# smart-switch.net
KiCad netlist of a schematic drawn in Altium Designer
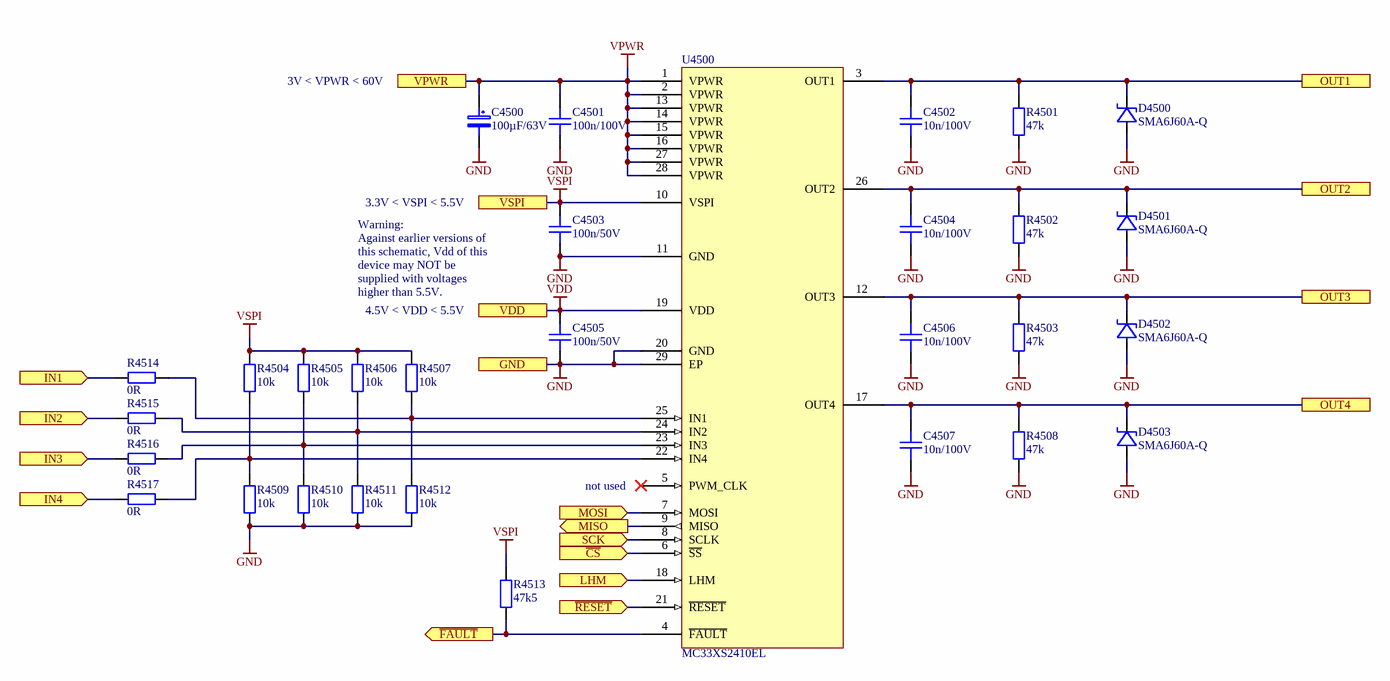
[diagram p0: smart-switch.SchDoc]

(export (version "E")
  (design (tool "Eeschema 10.0.6"))
  (components
    (comp (ref "C4500")
      (value "100µF/63V")
      (footprint "ELECTROLYTIC_CAP_PANASONIC_G")
      (description "SMD Electrolytic Capacitor")
      (fields (field (name "PART NUMBER") "EEE-TG1J101UP") (field (name "TOLERANCE") "+-20%"))
      (libsource (lib "OE750") (part "C_Pol"))
    )
    (comp (ref "C4501")
      (value "100n/100V")
      (footprint "CAPC1608X08N")
      (description "MLCC")
      (fields (field (name "PART NUMBER") "gen_C_ceramic_100n_100V_X7R_0603"))
      (libsource (lib "OE750") (part "C"))
    )
    (comp (ref "C4502")
      (value "10n/100V")
      (footprint "CAPC1608X08N")
      (description "MLCC")
      (fields (field (name "PART NUMBER") "gen_C_ceramic_10n_100V_X7R_0603"))
      (libsource (lib "OE750") (part "C"))
    )
    (comp (ref "C4503")
      (value "100n/50V")
      (footprint "CAPC1005X06N")
      (description "MLCC")
      (fields (field (name "PART NUMBER") "gen_C_ceramic_100n_50V_X7R_0402"))
      (libsource (lib "OE750") (part "C"))
    )
    (comp (ref "C4504")
      (value "10n/100V")
      (footprint "CAPC1608X08N")
      (description "MLCC")
      (fields (field (name "PART NUMBER") "gen_C_ceramic_10n_100V_X7R_0603"))
      (libsource (lib "OE750") (part "C"))
    )
    (comp (ref "C4505")
      (value "100n/50V")
      (footprint "CAPC1005X06N")
      (description "MLCC")
      (fields (field (name "PART NUMBER") "gen_C_ceramic_100n_50V_X7R_0402"))
      (libsource (lib "OE750") (part "C"))
    )
    (comp (ref "C4506")
      (value "10n/100V")
      (footprint "CAPC1608X08N")
      (description "MLCC")
      (fields (field (name "PART NUMBER") "gen_C_ceramic_10n_100V_X7R_0603"))
      (libsource (lib "OE750") (part "C"))
    )
    (comp (ref "C4507")
      (value "10n/100V")
      (footprint "CAPC1608X08N")
      (description "MLCC")
      (fields (field (name "PART NUMBER") "gen_C_ceramic_10n_100V_X7R_0603"))
      (libsource (lib "OE750") (part "C"))
    )
    (comp (ref "D4500")
      (value "SMA6J60A-Q")
      (footprint "BOURNS_DO-214AC_SMA")
      (description "TVS-Diode DO-214AC (SMA)")
      (fields (field (name "MANUFACTURER") "Bourns"))
      (libsource (lib "OE750") (part "D_TVS"))
    )
    (comp (ref "D4501")
      (value "SMA6J60A-Q")
      (footprint "BOURNS_DO-214AC_SMA")
      (description "TVS-Diode DO-214AC (SMA)")
      (fields (field (name "MANUFACTURER") "Bourns"))
      (libsource (lib "OE750") (part "D_TVS"))
    )
    (comp (ref "D4502")
      (value "SMA6J60A-Q")
      (footprint "BOURNS_DO-214AC_SMA")
      (description "TVS-Diode DO-214AC (SMA)")
      (fields (field (name "MANUFACTURER") "Bourns"))
      (libsource (lib "OE750") (part "D_TVS"))
    )
    (comp (ref "D4503")
      (value "SMA6J60A-Q")
      (footprint "BOURNS_DO-214AC_SMA")
      (description "TVS-Diode DO-214AC (SMA)")
      (fields (field (name "MANUFACTURER") "Bourns"))
      (libsource (lib "OE750") (part "D_TVS"))
    )
    (comp (ref "R4501")
      (value "47k")
      (footprint "RESC1005X04N")
      (description "SMD Resistor 47k 0402")
      (fields (field (name "PART NUMBER") "gen_R_47k_0402") (field (name "TOLERANCE") "1%"))
      (libsource (lib "OE750") (part "R"))
    )
    (comp (ref "R4502")
      (value "47k")
      (footprint "RESC1005X04N")
      (description "SMD Resistor 47k 0402")
      (fields (field (name "PART NUMBER") "gen_R_47k_0402") (field (name "TOLERANCE") "1%"))
      (libsource (lib "OE750") (part "R"))
    )
    (comp (ref "R4503")
      (value "47k")
      (footprint "RESC1005X04N")
      (description "SMD Resistor 47k 0402")
      (fields (field (name "PART NUMBER") "gen_R_47k_0402") (field (name "TOLERANCE") "1%"))
      (libsource (lib "OE750") (part "R"))
    )
    (comp (ref "R4504")
      (value "10k")
      (footprint "RESC1005X04N")
      (description "SMD Resistor 10k 0402")
      (fields (field (name "PART NUMBER") "gen_R_10k_0402") (field (name "TOLERANCE") "1%"))
      (libsource (lib "OE750") (part "R"))
    )
    (comp (ref "R4505")
      (value "10k")
      (footprint "RESC1005X04N")
      (description "SMD Resistor 10k 0402")
      (fields (field (name "PART NUMBER") "gen_R_10k_0402") (field (name "TOLERANCE") "1%"))
      (libsource (lib "OE750") (part "R"))
    )
    (comp (ref "R4506")
      (value "10k")
      (footprint "RESC1005X04N")
      (description "SMD Resistor 10k 0402")
      (fields (field (name "PART NUMBER") "gen_R_10k_0402") (field (name "TOLERANCE") "1%"))
      (libsource (lib "OE750") (part "R"))
    )
    (comp (ref "R4507")
      (value "10k")
      (footprint "RESC1005X04N")
      (description "SMD Resistor 10k 0402")
      (fields (field (name "PART NUMBER") "gen_R_10k_0402") (field (name "TOLERANCE") "1%"))
      (libsource (lib "OE750") (part "R"))
    )
    (comp (ref "R4508")
      (value "47k")
      (footprint "RESC1005X04N")
      (description "SMD Resistor 47k 0402")
      (fields (field (name "PART NUMBER") "gen_R_47k_0402") (field (name "TOLERANCE") "1%"))
      (libsource (lib "OE750") (part "R"))
    )
    (comp (ref "R4509")
      (value "10k")
      (footprint "RESC1005X04N")
      (description "SMD Resistor 10k 0402")
      (fields (field (name "PART NUMBER") "gen_R_10k_0402") (field (name "TOLERANCE") "1%"))
      (libsource (lib "OE750") (part "R"))
    )
    (comp (ref "R4510")
      (value "10k")
      (footprint "RESC1005X04N")
      (description "SMD Resistor 10k 0402")
      (fields (field (name "PART NUMBER") "gen_R_10k_0402") (field (name "TOLERANCE") "1%"))
      (libsource (lib "OE750") (part "R"))
    )
    (comp (ref "R4511")
      (value "10k")
      (footprint "RESC1005X04N")
      (description "SMD Resistor 10k 0402")
      (fields (field (name "PART NUMBER") "gen_R_10k_0402") (field (name "TOLERANCE") "1%"))
      (libsource (lib "OE750") (part "R"))
    )
    (comp (ref "R4512")
      (value "10k")
      (footprint "RESC1005X04N")
      (description "SMD Resistor 10k 0402")
      (fields (field (name "PART NUMBER") "gen_R_10k_0402") (field (name "TOLERANCE") "1%"))
      (libsource (lib "OE750") (part "R"))
    )
    (comp (ref "R4513")
      (value "47k5")
      (footprint "RESC1005X04N")
      (description "SMD Resistor 47k5 0402")
      (fields (field (name "PART NUMBER") "gen_R_47k5_0402") (field (name "TOLERANCE") "1%"))
      (libsource (lib "OE750") (part "R"))
    )
    (comp (ref "R4514")
      (value "0R")
      (footprint "RESC1005X04N")
      (description "SMD Resistor 0R 0402")
      (fields (field (name "PART NUMBER") "gen_R_0R_0402") (field (name "POWER") "0.063W"))
      (libsource (lib "OE750") (part "R"))
    )
    (comp (ref "R4515")
      (value "0R")
      (footprint "RESC1005X04N")
      (description "SMD Resistor 0R 0402")
      (fields (field (name "PART NUMBER") "gen_R_0R_0402") (field (name "POWER") "0.063W"))
      (libsource (lib "OE750") (part "R"))
    )
    (comp (ref "R4516")
      (value "0R")
      (footprint "RESC1005X04N")
      (description "SMD Resistor 0R 0402")
      (fields (field (name "PART NUMBER") "gen_R_0R_0402") (field (name "POWER") "0.063W"))
      (libsource (lib "OE750") (part "R"))
    )
    (comp (ref "R4517")
      (value "0R")
      (footprint "RESC1005X04N")
      (description "SMD Resistor 0R 0402")
      (fields (field (name "PART NUMBER") "gen_R_0R_0402") (field (name "POWER") "0.063W"))
      (libsource (lib "OE750") (part "R"))
    )
    (comp (ref "U4500")
      (value "MC33XS2410EL")
      (footprint "MC33XS2410EL")
      (description "Quad 100 mΩ / dual 50 mΩ, 3.0 V to 60 V high-side switch")
      (fields (field (name "MANUFACTURER") "NXP"))
      (libsource (lib "OE750") (part "MC33XS2410EL"))
    )
  )
  (nets
    (net (code "1") (name "/CS") (class "Default")
      (node (ref "U4500") (pin "6") (pinfunction "SS_6") (pintype "input"))
    )
    (net (code "2") (name "/FAULT") (class "Default")
      (node (ref "R4513") (pin "1") (pinfunction "1_1") (pintype "passive"))
      (node (ref "U4500") (pin "4") (pinfunction "FAULT_4") (pintype "open_collector"))
    )
    (net (code "3") (name "/IN1") (class "Default")
      (node (ref "R4514") (pin "1") (pinfunction "1_1") (pintype "passive"))
    )
    (net (code "4") (name "/IN2") (class "Default")
      (node (ref "R4515") (pin "1") (pinfunction "1_1") (pintype "passive"))
    )
    (net (code "5") (name "/IN3") (class "Default")
      (node (ref "R4516") (pin "1") (pinfunction "1_1") (pintype "passive"))
    )
    (net (code "6") (name "/IN4") (class "Default")
      (node (ref "R4517") (pin "1") (pinfunction "1_1") (pintype "passive"))
    )
    (net (code "7") (name "/LHM") (class "Default")
      (node (ref "U4500") (pin "18") (pinfunction "LHM_18") (pintype "input"))
    )
    (net (code "8") (name "/MISO") (class "Default")
      (node (ref "U4500") (pin "9") (pinfunction "MISO_9") (pintype "output"))
    )
    (net (code "9") (name "/MOSI") (class "Default")
      (node (ref "U4500") (pin "7") (pinfunction "MOSI_7") (pintype "input"))
    )
    (net (code "10") (name "/OUT1") (class "Default")
      (node (ref "C4502") (pin "2") (pinfunction "2_2") (pintype "passive"))
      (node (ref "D4500") (pin "1") (pinfunction "C_1") (pintype "passive"))
      (node (ref "R4501") (pin "2") (pinfunction "2_2") (pintype "passive"))
      (node (ref "U4500") (pin "3") (pinfunction "OUT1_3") (pintype "power_in"))
    )
    (net (code "11") (name "/OUT2") (class "Default")
      (node (ref "C4504") (pin "2") (pinfunction "2_2") (pintype "passive"))
      (node (ref "D4501") (pin "1") (pinfunction "C_1") (pintype "passive"))
      (node (ref "R4502") (pin "2") (pinfunction "2_2") (pintype "passive"))
      (node (ref "U4500") (pin "26") (pinfunction "OUT2_26") (pintype "power_in"))
    )
    (net (code "12") (name "/OUT3") (class "Default")
      (node (ref "C4506") (pin "2") (pinfunction "2_2") (pintype "passive"))
      (node (ref "D4502") (pin "1") (pinfunction "C_1") (pintype "passive"))
      (node (ref "R4503") (pin "2") (pinfunction "2_2") (pintype "passive"))
      (node (ref "U4500") (pin "12") (pinfunction "OUT3_12") (pintype "power_in"))
    )
    (net (code "13") (name "/OUT4") (class "Default")
      (node (ref "C4507") (pin "2") (pinfunction "2_2") (pintype "passive"))
      (node (ref "D4503") (pin "1") (pinfunction "C_1") (pintype "passive"))
      (node (ref "R4508") (pin "2") (pinfunction "2_2") (pintype "passive"))
      (node (ref "U4500") (pin "17") (pinfunction "OUT4_17") (pintype "power_in"))
    )
    (net (code "14") (name "/RESET") (class "Default")
      (node (ref "U4500") (pin "21") (pinfunction "RESET_21") (pintype "input"))
    )
    (net (code "15") (name "/SCK") (class "Default")
      (node (ref "U4500") (pin "8") (pinfunction "SCLK_8") (pintype "input"))
    )
    (net (code "16") (name "GND") (class "Default")
      (node (ref "C4500") (pin "2") (pinfunction "2_2") (pintype "passive"))
      (node (ref "C4501") (pin "1") (pinfunction "1_1") (pintype "passive"))
      (node (ref "C4502") (pin "1") (pinfunction "1_1") (pintype "passive"))
      (node (ref "C4503") (pin "1") (pinfunction "1_1") (pintype "passive"))
      (node (ref "C4504") (pin "1") (pinfunction "1_1") (pintype "passive"))
      (node (ref "C4505") (pin "1") (pinfunction "1_1") (pintype "passive"))
      (node (ref "C4506") (pin "1") (pinfunction "1_1") (pintype "passive"))
      (node (ref "C4507") (pin "1") (pinfunction "1_1") (pintype "passive"))
      (node (ref "D4500") (pin "2") (pinfunction "A_2") (pintype "passive"))
      (node (ref "D4501") (pin "2") (pinfunction "A_2") (pintype "passive"))
      (node (ref "D4502") (pin "2") (pinfunction "A_2") (pintype "passive"))
      (node (ref "D4503") (pin "2") (pinfunction "A_2") (pintype "passive"))
      (node (ref "R4501") (pin "1") (pinfunction "1_1") (pintype "passive"))
      (node (ref "R4502") (pin "1") (pinfunction "1_1") (pintype "passive"))
      (node (ref "R4503") (pin "1") (pinfunction "1_1") (pintype "passive"))
      (node (ref "R4508") (pin "1") (pinfunction "1_1") (pintype "passive"))
      (node (ref "R4509") (pin "1") (pinfunction "1_1") (pintype "passive"))
      (node (ref "R4510") (pin "1") (pinfunction "1_1") (pintype "passive"))
      (node (ref "R4511") (pin "1") (pinfunction "1_1") (pintype "passive"))
      (node (ref "R4512") (pin "1") (pinfunction "1_1") (pintype "passive"))
      (node (ref "U4500") (pin "11") (pinfunction "GND_11") (pintype "power_in"))
      (node (ref "U4500") (pin "20") (pinfunction "GND_20") (pintype "power_in"))
      (node (ref "U4500") (pin "29") (pinfunction "EP_29") (pintype "power_in"))
    )
    (net (code "17") (name "Net-(U4500-IN1)") (class "Default")
      (node (ref "R4507") (pin "1") (pinfunction "1_1") (pintype "passive"))
      (node (ref "R4512") (pin "2") (pinfunction "2_2") (pintype "passive"))
      (node (ref "R4514") (pin "2") (pinfunction "2_2") (pintype "passive"))
      (node (ref "U4500") (pin "25") (pinfunction "IN1_25") (pintype "input"))
    )
    (net (code "18") (name "Net-(U4500-IN2)") (class "Default")
      (node (ref "R4506") (pin "1") (pinfunction "1_1") (pintype "passive"))
      (node (ref "R4511") (pin "2") (pinfunction "2_2") (pintype "passive"))
      (node (ref "R4515") (pin "2") (pinfunction "2_2") (pintype "passive"))
      (node (ref "U4500") (pin "24") (pinfunction "IN2_24") (pintype "input"))
    )
    (net (code "19") (name "Net-(U4500-IN3)") (class "Default")
      (node (ref "R4505") (pin "1") (pinfunction "1_1") (pintype "passive"))
      (node (ref "R4510") (pin "2") (pinfunction "2_2") (pintype "passive"))
      (node (ref "R4516") (pin "2") (pinfunction "2_2") (pintype "passive"))
      (node (ref "U4500") (pin "23") (pinfunction "IN3_23") (pintype "input"))
    )
    (net (code "20") (name "Net-(U4500-IN4)") (class "Default")
      (node (ref "R4504") (pin "1") (pinfunction "1_1") (pintype "passive"))
      (node (ref "R4509") (pin "2") (pinfunction "2_2") (pintype "passive"))
      (node (ref "R4517") (pin "2") (pinfunction "2_2") (pintype "passive"))
      (node (ref "U4500") (pin "22") (pinfunction "IN4_22") (pintype "input"))
    )
    (net (code "21") (name "VDD") (class "Default")
      (node (ref "C4505") (pin "2") (pinfunction "2_2") (pintype "passive"))
      (node (ref "U4500") (pin "19") (pinfunction "VDD_19") (pintype "power_in"))
    )
    (net (code "22") (name "VPWR") (class "Default")
      (node (ref "C4500") (pin "1") (pinfunction "1_1") (pintype "passive"))
      (node (ref "C4501") (pin "2") (pinfunction "2_2") (pintype "passive"))
      (node (ref "U4500") (pin "1") (pinfunction "VPWR_1") (pintype "power_in"))
      (node (ref "U4500") (pin "13") (pinfunction "VPWR_13") (pintype "power_in"))
      (node (ref "U4500") (pin "14") (pinfunction "VPWR_14") (pintype "power_in"))
      (node (ref "U4500") (pin "15") (pinfunction "VPWR_15") (pintype "power_in"))
      (node (ref "U4500") (pin "16") (pinfunction "VPWR_16") (pintype "power_in"))
      (node (ref "U4500") (pin "2") (pinfunction "VPWR_2") (pintype "power_in"))
      (node (ref "U4500") (pin "27") (pinfunction "VPWR_27") (pintype "power_in"))
      (node (ref "U4500") (pin "28") (pinfunction "VPWR_28") (pintype "power_in"))
    )
    (net (code "23") (name "VSPI") (class "Default")
      (node (ref "C4503") (pin "2") (pinfunction "2_2") (pintype "passive"))
      (node (ref "R4504") (pin "2") (pinfunction "2_2") (pintype "passive"))
      (node (ref "R4505") (pin "2") (pinfunction "2_2") (pintype "passive"))
      (node (ref "R4506") (pin "2") (pinfunction "2_2") (pintype "passive"))
      (node (ref "R4507") (pin "2") (pinfunction "2_2") (pintype "passive"))
      (node (ref "R4513") (pin "2") (pinfunction "2_2") (pintype "passive"))
      (node (ref "U4500") (pin "10") (pinfunction "VSPI_10") (pintype "power_in"))
    )
    (net (code "24") (name "unconnected-(U4500-PWM_CLK-Pad5)") (class "Default")
      (node (ref "U4500") (pin "5") (pinfunction "PWM_CLK_5") (pintype "input+no_connect"))
    )
  )
)
